# Yaoji.net
KiCad netlist of a schematic drawn in Altium Designer
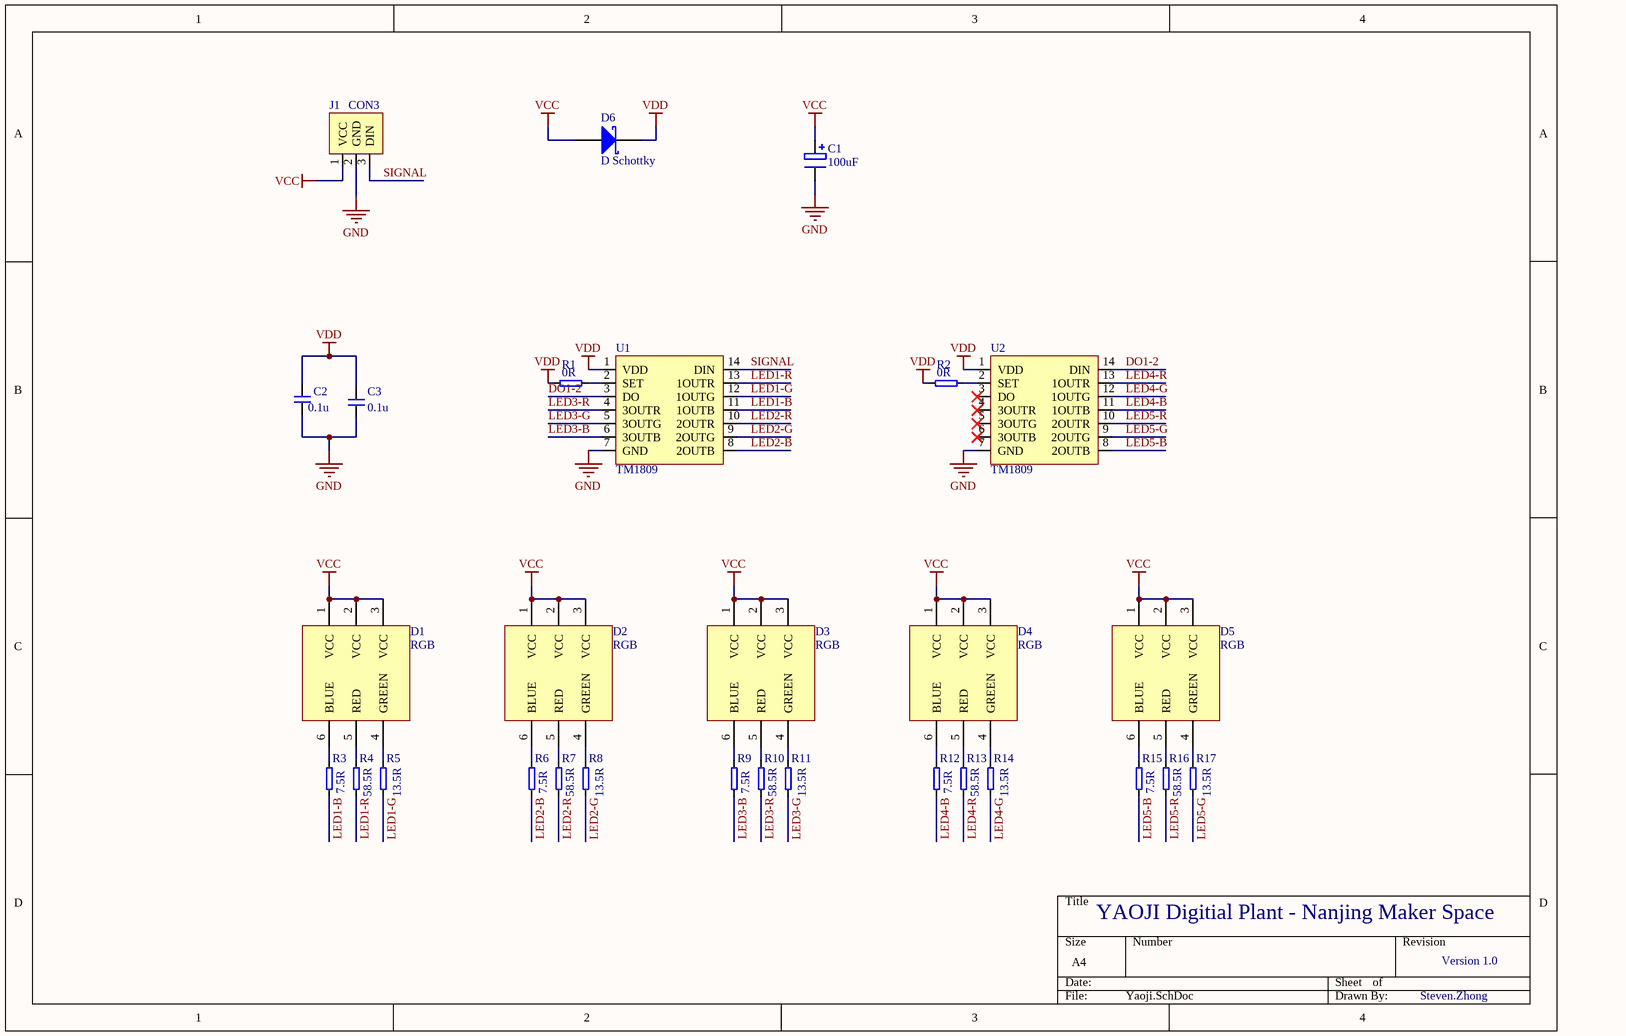
[diagram p0: Yaoji.SchDoc]

(export (version "E")
  (design (tool "Eeschema 10.0.6"))
  (components
    (comp (ref "C1")
      (value "100uF")
      (footprint "CAP_TA3216-18N")
      (description "Capacitor with pole")
      (fields (field (name "Comment") "Cap2") (field (name "PUBLISHER") "Altium Limited"))
      (libsource (lib "iLib Device") (part "Cap2"))
    )
    (comp (ref "C2") (value "0.1u") (footprint "0603") (libsource (lib "YAOJI") (part "Cap")))
    (comp (ref "C3") (value "0.1u") (footprint "0603") (libsource (lib "YAOJI") (part "Cap")))
    (comp (ref "D1") (value "RGB") (footprint "5050RGB") (libsource (lib "YAOJI") (part "RGB")))
    (comp (ref "D2") (value "RGB") (footprint "5050RGB") (libsource (lib "YAOJI") (part "RGB")))
    (comp (ref "D3") (value "RGB") (footprint "5050RGB") (libsource (lib "YAOJI") (part "RGB")))
    (comp (ref "D4") (value "RGB") (footprint "5050RGB") (libsource (lib "YAOJI") (part "RGB")))
    (comp (ref "D5") (value "RGB") (footprint "5050RGB") (libsource (lib "YAOJI") (part "RGB")))
    (comp (ref "D6")
      (value "D Schottky")
      (footprint "SMB-DIODE")
      (description "Schottky Diode")
      (fields (field (name "PUBLISHER") "Altium Limited"))
      (libsource (lib "iLib Device") (part "D Schottky"))
    )
    (comp (ref "J1") (value "CON3") (footprint "CON3") (libsource (lib "YAOJI") (part "CON3")))
    (comp (ref "R1") (value "0R") (footprint "0603") (libsource (lib "YAOJI") (part "Res")))
    (comp (ref "R2") (value "0R") (footprint "0603") (libsource (lib "YAOJI") (part "Res")))
    (comp (ref "R3") (value "7.5R") (footprint "0603") (libsource (lib "YAOJI") (part "Res")))
    (comp (ref "R4") (value "58.5R") (footprint "0603") (libsource (lib "YAOJI") (part "Res")))
    (comp (ref "R5") (value "13.5R") (footprint "0603") (libsource (lib "YAOJI") (part "Res")))
    (comp (ref "R6") (value "7.5R") (footprint "0603") (libsource (lib "YAOJI") (part "Res")))
    (comp (ref "R7") (value "58.5R") (footprint "0603") (libsource (lib "YAOJI") (part "Res")))
    (comp (ref "R8") (value "13.5R") (footprint "0603") (libsource (lib "YAOJI") (part "Res")))
    (comp (ref "R9") (value "7.5R") (footprint "0603") (libsource (lib "YAOJI") (part "Res")))
    (comp (ref "R10") (value "58.5R") (footprint "0603") (libsource (lib "YAOJI") (part "Res")))
    (comp (ref "R11") (value "13.5R") (footprint "0603") (libsource (lib "YAOJI") (part "Res")))
    (comp (ref "R12") (value "7.5R") (footprint "0603") (libsource (lib "YAOJI") (part "Res")))
    (comp (ref "R13") (value "58.5R") (footprint "0603") (libsource (lib "YAOJI") (part "Res")))
    (comp (ref "R14") (value "13.5R") (footprint "0603") (libsource (lib "YAOJI") (part "Res")))
    (comp (ref "R15") (value "7.5R") (footprint "0603") (libsource (lib "YAOJI") (part "Res")))
    (comp (ref "R16") (value "58.5R") (footprint "0603") (libsource (lib "YAOJI") (part "Res")))
    (comp (ref "R17") (value "13.5R") (footprint "0603") (libsource (lib "YAOJI") (part "Res")))
    (comp (ref "U1") (value "TM1809") (footprint "SO-14") (libsource (lib "YAOJI") (part "TM1809")))
    (comp (ref "U2") (value "TM1809") (footprint "SO-14") (libsource (lib "YAOJI") (part "TM1809")))
  )
  (nets
    (net (code "1") (name "/DO1-2") (class "Default")
      (node (ref "U1") (pin "3") (pinfunction "DO_3") (pintype "passive"))
      (node (ref "U2") (pin "14") (pinfunction "DIN_14") (pintype "passive"))
    )
    (net (code "2") (name "/LED1-B") (class "Default")
      (node (ref "R3") (pin "1") (pinfunction "1_1") (pintype "passive"))
      (node (ref "U1") (pin "11") (pinfunction "1OUTB_11") (pintype "passive"))
    )
    (net (code "3") (name "/LED1-G") (class "Default")
      (node (ref "R5") (pin "2") (pinfunction "2_2") (pintype "passive"))
      (node (ref "U1") (pin "12") (pinfunction "1OUTG_12") (pintype "passive"))
    )
    (net (code "4") (name "/LED1-R") (class "Default")
      (node (ref "R4") (pin "2") (pinfunction "2_2") (pintype "passive"))
      (node (ref "U1") (pin "13") (pinfunction "1OUTR_13") (pintype "passive"))
    )
    (net (code "5") (name "/LED2-B") (class "Default")
      (node (ref "R6") (pin "1") (pinfunction "1_1") (pintype "passive"))
      (node (ref "U1") (pin "8") (pinfunction "2OUTB_8") (pintype "passive"))
    )
    (net (code "6") (name "/LED2-G") (class "Default")
      (node (ref "R8") (pin "2") (pinfunction "2_2") (pintype "passive"))
      (node (ref "U1") (pin "9") (pinfunction "2OUTG_9") (pintype "passive"))
    )
    (net (code "7") (name "/LED2-R") (class "Default")
      (node (ref "R7") (pin "2") (pinfunction "2_2") (pintype "passive"))
      (node (ref "U1") (pin "10") (pinfunction "2OUTR_10") (pintype "passive"))
    )
    (net (code "8") (name "/LED3-B") (class "Default")
      (node (ref "R9") (pin "1") (pinfunction "1_1") (pintype "passive"))
      (node (ref "U1") (pin "6") (pinfunction "3OUTB_6") (pintype "passive"))
    )
    (net (code "9") (name "/LED3-G") (class "Default")
      (node (ref "R11") (pin "2") (pinfunction "2_2") (pintype "passive"))
      (node (ref "U1") (pin "5") (pinfunction "3OUTG_5") (pintype "passive"))
    )
    (net (code "10") (name "/LED3-R") (class "Default")
      (node (ref "R10") (pin "2") (pinfunction "2_2") (pintype "passive"))
      (node (ref "U1") (pin "4") (pinfunction "3OUTR_4") (pintype "passive"))
    )
    (net (code "11") (name "/LED4-B") (class "Default")
      (node (ref "R12") (pin "1") (pinfunction "1_1") (pintype "passive"))
      (node (ref "U2") (pin "11") (pinfunction "1OUTB_11") (pintype "passive"))
    )
    (net (code "12") (name "/LED4-G") (class "Default")
      (node (ref "R14") (pin "2") (pinfunction "2_2") (pintype "passive"))
      (node (ref "U2") (pin "12") (pinfunction "1OUTG_12") (pintype "passive"))
    )
    (net (code "13") (name "/LED4-R") (class "Default")
      (node (ref "R13") (pin "2") (pinfunction "2_2") (pintype "passive"))
      (node (ref "U2") (pin "13") (pinfunction "1OUTR_13") (pintype "passive"))
    )
    (net (code "14") (name "/LED5-B") (class "Default")
      (node (ref "R15") (pin "1") (pinfunction "1_1") (pintype "passive"))
      (node (ref "U2") (pin "8") (pinfunction "2OUTB_8") (pintype "passive"))
    )
    (net (code "15") (name "/LED5-G") (class "Default")
      (node (ref "R17") (pin "2") (pinfunction "2_2") (pintype "passive"))
      (node (ref "U2") (pin "9") (pinfunction "2OUTG_9") (pintype "passive"))
    )
    (net (code "16") (name "/LED5-R") (class "Default")
      (node (ref "R16") (pin "2") (pinfunction "2_2") (pintype "passive"))
      (node (ref "U2") (pin "10") (pinfunction "2OUTR_10") (pintype "passive"))
    )
    (net (code "17") (name "/SIGNAL") (class "Default")
      (node (ref "J1") (pin "3") (pinfunction "DIN_3") (pintype "passive"))
      (node (ref "U1") (pin "14") (pinfunction "DIN_14") (pintype "passive"))
    )
    (net (code "18") (name "GND") (class "Default")
      (node (ref "C1") (pin "2") (pinfunction "2_2") (pintype "passive"))
      (node (ref "C2") (pin "1") (pinfunction "1_1") (pintype "passive"))
      (node (ref "C3") (pin "1") (pinfunction "1_1") (pintype "passive"))
      (node (ref "J1") (pin "2") (pinfunction "GND_2") (pintype "passive"))
      (node (ref "U1") (pin "7") (pinfunction "GND_7") (pintype "passive"))
      (node (ref "U2") (pin "7") (pinfunction "GND_7") (pintype "passive"))
    )
    (net (code "19") (name "Net-(D1-BLUE)") (class "Default")
      (node (ref "D1") (pin "6") (pinfunction "BLUE_6") (pintype "passive"))
      (node (ref "R3") (pin "2") (pinfunction "2_2") (pintype "passive"))
    )
    (net (code "20") (name "Net-(D1-GREEN)") (class "Default")
      (node (ref "D1") (pin "4") (pinfunction "GREEN_4") (pintype "passive"))
      (node (ref "R5") (pin "1") (pinfunction "1_1") (pintype "passive"))
    )
    (net (code "21") (name "Net-(D1-RED)") (class "Default")
      (node (ref "D1") (pin "5") (pinfunction "RED_5") (pintype "passive"))
      (node (ref "R4") (pin "1") (pinfunction "1_1") (pintype "passive"))
    )
    (net (code "22") (name "Net-(D2-BLUE)") (class "Default")
      (node (ref "D2") (pin "6") (pinfunction "BLUE_6") (pintype "passive"))
      (node (ref "R6") (pin "2") (pinfunction "2_2") (pintype "passive"))
    )
    (net (code "23") (name "Net-(D2-GREEN)") (class "Default")
      (node (ref "D2") (pin "4") (pinfunction "GREEN_4") (pintype "passive"))
      (node (ref "R8") (pin "1") (pinfunction "1_1") (pintype "passive"))
    )
    (net (code "24") (name "Net-(D2-RED)") (class "Default")
      (node (ref "D2") (pin "5") (pinfunction "RED_5") (pintype "passive"))
      (node (ref "R7") (pin "1") (pinfunction "1_1") (pintype "passive"))
    )
    (net (code "25") (name "Net-(D3-BLUE)") (class "Default")
      (node (ref "D3") (pin "6") (pinfunction "BLUE_6") (pintype "passive"))
      (node (ref "R9") (pin "2") (pinfunction "2_2") (pintype "passive"))
    )
    (net (code "26") (name "Net-(D3-GREEN)") (class "Default")
      (node (ref "D3") (pin "4") (pinfunction "GREEN_4") (pintype "passive"))
      (node (ref "R11") (pin "1") (pinfunction "1_1") (pintype "passive"))
    )
    (net (code "27") (name "Net-(D3-RED)") (class "Default")
      (node (ref "D3") (pin "5") (pinfunction "RED_5") (pintype "passive"))
      (node (ref "R10") (pin "1") (pinfunction "1_1") (pintype "passive"))
    )
    (net (code "28") (name "Net-(D4-BLUE)") (class "Default")
      (node (ref "D4") (pin "6") (pinfunction "BLUE_6") (pintype "passive"))
      (node (ref "R12") (pin "2") (pinfunction "2_2") (pintype "passive"))
    )
    (net (code "29") (name "Net-(D4-GREEN)") (class "Default")
      (node (ref "D4") (pin "4") (pinfunction "GREEN_4") (pintype "passive"))
      (node (ref "R14") (pin "1") (pinfunction "1_1") (pintype "passive"))
    )
    (net (code "30") (name "Net-(D4-RED)") (class "Default")
      (node (ref "D4") (pin "5") (pinfunction "RED_5") (pintype "passive"))
      (node (ref "R13") (pin "1") (pinfunction "1_1") (pintype "passive"))
    )
    (net (code "31") (name "Net-(D5-BLUE)") (class "Default")
      (node (ref "D5") (pin "6") (pinfunction "BLUE_6") (pintype "passive"))
      (node (ref "R15") (pin "2") (pinfunction "2_2") (pintype "passive"))
    )
    (net (code "32") (name "Net-(D5-GREEN)") (class "Default")
      (node (ref "D5") (pin "4") (pinfunction "GREEN_4") (pintype "passive"))
      (node (ref "R17") (pin "1") (pinfunction "1_1") (pintype "passive"))
    )
    (net (code "33") (name "Net-(D5-RED)") (class "Default")
      (node (ref "D5") (pin "5") (pinfunction "RED_5") (pintype "passive"))
      (node (ref "R16") (pin "1") (pinfunction "1_1") (pintype "passive"))
    )
    (net (code "34") (name "Net-(U1-SET)") (class "Default")
      (node (ref "R1") (pin "2") (pinfunction "2_2") (pintype "passive"))
      (node (ref "U1") (pin "2") (pinfunction "SET_2") (pintype "passive"))
    )
    (net (code "35") (name "Net-(U2-SET)") (class "Default")
      (node (ref "R2") (pin "2") (pinfunction "2_2") (pintype "passive"))
      (node (ref "U2") (pin "2") (pinfunction "SET_2") (pintype "passive"))
    )
    (net (code "36") (name "VCC") (class "Default")
      (node (ref "C1") (pin "1") (pinfunction "1_1") (pintype "passive"))
      (node (ref "D1") (pin "1") (pinfunction "VCC_1") (pintype "passive"))
      (node (ref "D1") (pin "2") (pinfunction "VCC_2") (pintype "passive"))
      (node (ref "D1") (pin "3") (pinfunction "VCC_3") (pintype "passive"))
      (node (ref "D2") (pin "1") (pinfunction "VCC_1") (pintype "passive"))
      (node (ref "D2") (pin "2") (pinfunction "VCC_2") (pintype "passive"))
      (node (ref "D2") (pin "3") (pinfunction "VCC_3") (pintype "passive"))
      (node (ref "D3") (pin "1") (pinfunction "VCC_1") (pintype "passive"))
      (node (ref "D3") (pin "2") (pinfunction "VCC_2") (pintype "passive"))
      (node (ref "D3") (pin "3") (pinfunction "VCC_3") (pintype "passive"))
      (node (ref "D4") (pin "1") (pinfunction "VCC_1") (pintype "passive"))
      (node (ref "D4") (pin "2") (pinfunction "VCC_2") (pintype "passive"))
      (node (ref "D4") (pin "3") (pinfunction "VCC_3") (pintype "passive"))
      (node (ref "D5") (pin "1") (pinfunction "VCC_1") (pintype "passive"))
      (node (ref "D5") (pin "2") (pinfunction "VCC_2") (pintype "passive"))
      (node (ref "D5") (pin "3") (pinfunction "VCC_3") (pintype "passive"))
      (node (ref "D6") (pin "1") (pinfunction "A_1") (pintype "passive"))
      (node (ref "J1") (pin "1") (pinfunction "VCC_1") (pintype "passive"))
    )
    (net (code "37") (name "VDD") (class "Default")
      (node (ref "C2") (pin "2") (pinfunction "2_2") (pintype "passive"))
      (node (ref "C3") (pin "2") (pinfunction "2_2") (pintype "passive"))
      (node (ref "D6") (pin "2") (pinfunction "K_2") (pintype "passive"))
      (node (ref "R1") (pin "1") (pinfunction "1_1") (pintype "passive"))
      (node (ref "R2") (pin "1") (pinfunction "1_1") (pintype "passive"))
      (node (ref "U1") (pin "1") (pinfunction "VDD_1") (pintype "passive"))
      (node (ref "U2") (pin "1") (pinfunction "VDD_1") (pintype "passive"))
    )
    (net (code "38") (name "unconnected-(U2-3OUTB-Pad6)") (class "Default")
      (node (ref "U2") (pin "6") (pinfunction "3OUTB_6") (pintype "passive+no_connect"))
    )
    (net (code "39") (name "unconnected-(U2-3OUTG-Pad5)") (class "Default")
      (node (ref "U2") (pin "5") (pinfunction "3OUTG_5") (pintype "passive+no_connect"))
    )
    (net (code "40") (name "unconnected-(U2-3OUTR-Pad4)") (class "Default")
      (node (ref "U2") (pin "4") (pinfunction "3OUTR_4") (pintype "passive+no_connect"))
    )
    (net (code "41") (name "unconnected-(U2-DO-Pad3)") (class "Default")
      (node (ref "U2") (pin "3") (pinfunction "DO_3") (pintype "passive+no_connect"))
    )
  )
)
